# Sheet1.net
KiCad netlist of a schematic drawn in Altium Designer
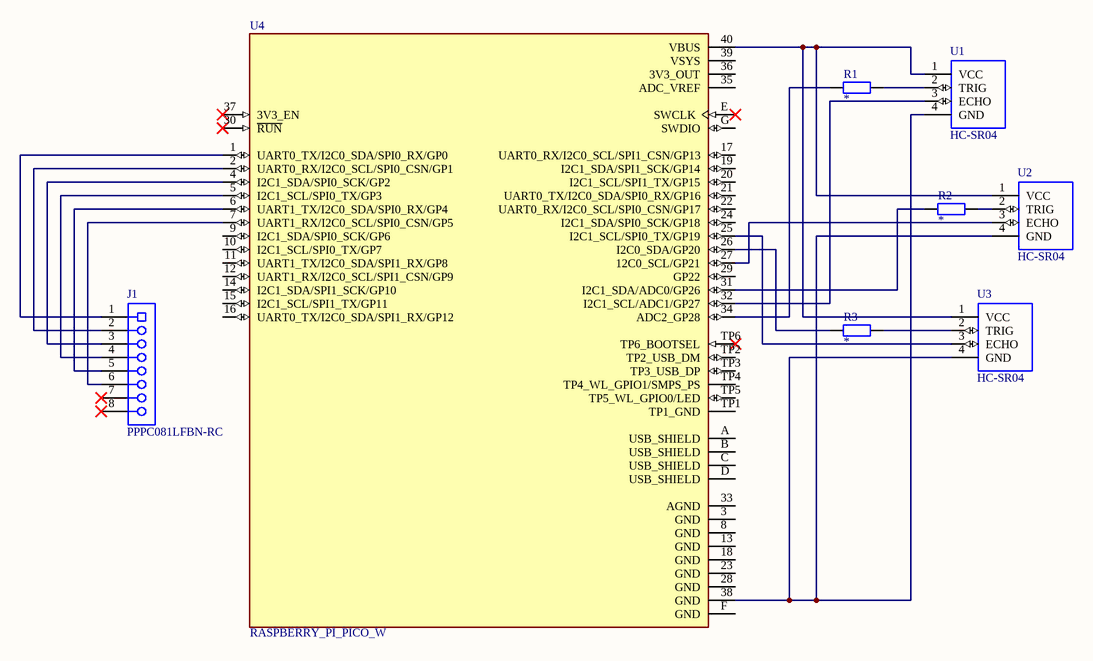
[diagram p0: Sheet1.SchDoc]

(export (version "E")
  (design (tool "Eeschema 10.0.6"))
  (components
    (comp (ref "J1")
      (value "PPPC081LFBN-RC")
      (footprint "SLIN-PPPC081LFBN-RC_V")
      (fields (field (name "MANUFACTURER") "Sullins"))
      (libsource (lib "Akansha Aggarwal") (part "CN-1P-F-R8"))
    )
    (comp (ref "R1")
      (value "*")
      (footprint "AXIAL-0.4")
      (description "Through hole resistor")
      (fields (field (name "PUBLISHER") "Altium Limited"))
      (libsource (lib "EE209_Library") (part "Res_TH_0AX4"))
    )
    (comp (ref "R2")
      (value "*")
      (footprint "AXIAL-0.4")
      (description "Through hole resistor")
      (fields (field (name "PUBLISHER") "Altium Limited"))
      (libsource (lib "EE209_Library") (part "Res_TH_0AX4"))
    )
    (comp (ref "R3")
      (value "*")
      (footprint "AXIAL-0.4")
      (description "Through hole resistor")
      (fields (field (name "PUBLISHER") "Altium Limited"))
      (libsource (lib "EE209_Library") (part "Res_TH_0AX4"))
    )
    (comp (ref "U1")
      (value "HC-SR04")
      (footprint "XCVR_HC-SR04")
      (description "Ultrasonic Sensor Module")
      (libsource (lib "HC-SR04") (part "HC-SR04"))
    )
    (comp (ref "U2")
      (value "HC-SR04")
      (footprint "XCVR_HC-SR04")
      (description "Ultrasonic Sensor Module")
      (libsource (lib "HC-SR04") (part "HC-SR04"))
    )
    (comp (ref "U3")
      (value "HC-SR04")
      (footprint "XCVR_HC-SR04")
      (description "Ultrasonic Sensor Module")
      (libsource (lib "HC-SR04") (part "HC-SR04"))
    )
    (comp (ref "U4")
      (value "RASPBERRY_PI_PICO_W")
      (footprint "MODULE_RASPBERRY_PI_PICO_W")
      (fields (field (name "MF") "Raspberry Pi") (field (name "MP") "RASPBERRY PI PICO W"))
      (libsource (lib "RASPBERRY_PI_PICO_W") (part "RASPBERRY_PI_PICO_W"))
    )
  )
  (nets
    (net (code "1") (name "Net-(U1-ECHO)") (class "Default")
      (node (ref "U1") (pin "3") (pinfunction "ECHO_3") (pintype "bidirectional"))
      (node (ref "U4") (pin "32") (pinfunction "I2C1_SCL/ADC1/GP27_32") (pintype "bidirectional"))
    )
    (net (code "2") (name "Net-(U1-GND)") (class "Default")
      (node (ref "U1") (pin "4") (pinfunction "GND_4") (pintype "power_in"))
      (node (ref "U2") (pin "4") (pinfunction "GND_4") (pintype "power_in"))
      (node (ref "U3") (pin "4") (pinfunction "GND_4") (pintype "power_in"))
      (node (ref "U4") (pin "38") (pinfunction "GND_38") (pintype "power_in"))
    )
    (net (code "3") (name "Net-(U1-TRIG)") (class "Default")
      (node (ref "R1") (pin "2") (pinfunction "2_2") (pintype "passive"))
      (node (ref "U1") (pin "2") (pinfunction "TRIG_2") (pintype "bidirectional"))
    )
    (net (code "4") (name "Net-(U1-VCC)") (class "Default")
      (node (ref "U1") (pin "1") (pinfunction "VCC_1") (pintype "power_in"))
      (node (ref "U2") (pin "1") (pinfunction "VCC_1") (pintype "power_in"))
      (node (ref "U3") (pin "1") (pinfunction "VCC_1") (pintype "power_in"))
      (node (ref "U4") (pin "40") (pinfunction "VBUS_40") (pintype "power_in"))
    )
    (net (code "5") (name "Net-(U2-ECHO)") (class "Default")
      (node (ref "U2") (pin "3") (pinfunction "ECHO_3") (pintype "bidirectional"))
      (node (ref "U4") (pin "27") (pinfunction "12C0_SCL/GP21_27") (pintype "bidirectional"))
    )
    (net (code "6") (name "Net-(U2-TRIG)") (class "Default")
      (node (ref "R2") (pin "2") (pinfunction "2_2") (pintype "passive"))
      (node (ref "U2") (pin "2") (pinfunction "TRIG_2") (pintype "bidirectional"))
    )
    (net (code "7") (name "Net-(U3-ECHO)") (class "Default")
      (node (ref "U3") (pin "3") (pinfunction "ECHO_3") (pintype "bidirectional"))
      (node (ref "U4") (pin "25") (pinfunction "I2C1_SCL/SPI0_TX/GP19_25") (pintype "bidirectional"))
    )
    (net (code "8") (name "Net-(U3-TRIG)") (class "Default")
      (node (ref "R3") (pin "2") (pinfunction "2_2") (pintype "passive"))
      (node (ref "U3") (pin "2") (pinfunction "TRIG_2") (pintype "bidirectional"))
    )
    (net (code "9") (name "Net-(U4-ADC2_GP28)") (class "Default")
      (node (ref "R1") (pin "1") (pinfunction "1_1") (pintype "passive"))
      (node (ref "U4") (pin "34") (pinfunction "ADC2_GP28_34") (pintype "bidirectional"))
    )
    (net (code "10") (name "Net-(U4-I2C0_SDA{slash}GP20)") (class "Default")
      (node (ref "R3") (pin "1") (pinfunction "1_1") (pintype "passive"))
      (node (ref "U4") (pin "26") (pinfunction "I2C0_SDA/GP20_26") (pintype "bidirectional"))
    )
    (net (code "11") (name "Net-(U4-I2C1_SCL{slash}SPI0_TX{slash}GP3)") (class "Default")
      (node (ref "J1") (pin "4") (pinfunction "4_4") (pintype "passive"))
      (node (ref "U4") (pin "5") (pinfunction "I2C1_SCL/SPI0_TX/GP3_5") (pintype "bidirectional"))
    )
    (net (code "12") (name "Net-(U4-I2C1_SDA{slash}ADC0{slash}GP26)") (class "Default")
      (node (ref "R2") (pin "1") (pinfunction "1_1") (pintype "passive"))
      (node (ref "U4") (pin "31") (pinfunction "I2C1_SDA/ADC0/GP26_31") (pintype "bidirectional"))
    )
    (net (code "13") (name "Net-(U4-I2C1_SDA{slash}SPI0_SCK{slash}GP2)") (class "Default")
      (node (ref "J1") (pin "3") (pinfunction "3_3") (pintype "passive"))
      (node (ref "U4") (pin "4") (pinfunction "I2C1_SDA/SPI0_SCK/GP2_4") (pintype "bidirectional"))
    )
    (net (code "14") (name "Net-(U4-UART0_RX{slash}I2C0_SCL{slash}SPI0_CSN{slash}GP1)") (class "Default")
      (node (ref "J1") (pin "2") (pinfunction "2_2") (pintype "passive"))
      (node (ref "U4") (pin "2") (pinfunction "UART0_RX/I2C0_SCL/SPI0_CSN/GP1_2") (pintype "bidirectional"))
    )
    (net (code "15") (name "Net-(U4-UART0_TX{slash}I2C0_SDA{slash}SPI0_RX{slash}GP0)") (class "Default")
      (node (ref "J1") (pin "1") (pinfunction "1_1") (pintype "passive"))
      (node (ref "U4") (pin "1") (pinfunction "UART0_TX/I2C0_SDA/SPI0_RX/GP0_1") (pintype "bidirectional"))
    )
    (net (code "16") (name "Net-(U4-UART1_RX{slash}I2C0_SCL{slash}SPI0_CSN{slash}GP5)") (class "Default")
      (node (ref "J1") (pin "6") (pinfunction "6_6") (pintype "passive"))
      (node (ref "U4") (pin "7") (pinfunction "UART1_RX/I2C0_SCL/SPI0_CSN/GP5_7") (pintype "bidirectional"))
    )
    (net (code "17") (name "Net-(U4-UART1_TX{slash}I2C0_SDA{slash}SPI0_RX{slash}GP4)") (class "Default")
      (node (ref "J1") (pin "5") (pinfunction "5_5") (pintype "passive"))
      (node (ref "U4") (pin "6") (pinfunction "UART1_TX/I2C0_SDA/SPI0_RX/GP4_6") (pintype "bidirectional"))
    )
    (net (code "18") (name "unconnected-(J1-Pad7)") (class "Default")
      (node (ref "J1") (pin "7") (pinfunction "7_7") (pintype "passive+no_connect"))
    )
    (net (code "19") (name "unconnected-(J1-Pad8)") (class "Default")
      (node (ref "J1") (pin "8") (pinfunction "8_8") (pintype "passive+no_connect"))
    )
    (net (code "20") (name "unconnected-(U4-3V3_EN-Pad37)") (class "Default")
      (node (ref "U4") (pin "37") (pinfunction "3V3_EN_37") (pintype "input+no_connect"))
    )
    (net (code "21") (name "unconnected-(U4-3V3_OUT-Pad36)") (class "Default")
      (node (ref "U4") (pin "36") (pinfunction "3V3_OUT_36") (pintype "power_in"))
    )
    (net (code "22") (name "unconnected-(U4-ADC_VREF-Pad35)") (class "Default")
      (node (ref "U4") (pin "35") (pinfunction "ADC_VREF_35") (pintype "power_in"))
    )
    (net (code "23") (name "unconnected-(U4-AGND-Pad33)") (class "Default")
      (node (ref "U4") (pin "33") (pinfunction "AGND_33") (pintype "power_in"))
    )
    (net (code "24") (name "unconnected-(U4-GND-Pad3)") (class "Default")
      (node (ref "U4") (pin "3") (pinfunction "GND_3") (pintype "power_in"))
    )
    (net (code "25") (name "unconnected-(U4-GND-Pad8)") (class "Default")
      (node (ref "U4") (pin "8") (pinfunction "GND_8") (pintype "power_in"))
    )
    (net (code "26") (name "unconnected-(U4-GND-Pad13)") (class "Default")
      (node (ref "U4") (pin "13") (pinfunction "GND_13") (pintype "power_in"))
    )
    (net (code "27") (name "unconnected-(U4-GND-Pad18)") (class "Default")
      (node (ref "U4") (pin "18") (pinfunction "GND_18") (pintype "power_in"))
    )
    (net (code "28") (name "unconnected-(U4-GND-Pad23)") (class "Default")
      (node (ref "U4") (pin "23") (pinfunction "GND_23") (pintype "power_in"))
    )
    (net (code "29") (name "unconnected-(U4-GND-Pad28)") (class "Default")
      (node (ref "U4") (pin "28") (pinfunction "GND_28") (pintype "power_in"))
    )
    (net (code "30") (name "unconnected-(U4-GND-PadF)") (class "Default")
      (node (ref "U4") (pin "F") (pinfunction "GND_F") (pintype "power_in"))
    )
    (net (code "31") (name "unconnected-(U4-GP22-Pad29)") (class "Default")
      (node (ref "U4") (pin "29") (pinfunction "GP22_29") (pintype "bidirectional"))
    )
    (net (code "32") (name "unconnected-(U4-I2C1_SCL{slash}SPI0_TX{slash}GP7-Pad10)") (class "Default")
      (node (ref "U4") (pin "10") (pinfunction "I2C1_SCL/SPI0_TX/GP7_10") (pintype "bidirectional"))
    )
    (net (code "33") (name "unconnected-(U4-I2C1_SCL{slash}SPI1_TX{slash}GP11-Pad15)") (class "Default")
      (node (ref "U4") (pin "15") (pinfunction "I2C1_SCL/SPI1_TX/GP11_15") (pintype "bidirectional"))
    )
    (net (code "34") (name "unconnected-(U4-I2C1_SCL{slash}SPI1_TX{slash}GP15-Pad20)") (class "Default")
      (node (ref "U4") (pin "20") (pinfunction "I2C1_SCL/SPI1_TX/GP15_20") (pintype "bidirectional"))
    )
    (net (code "35") (name "unconnected-(U4-I2C1_SDA{slash}SPI0_SCK{slash}GP6-Pad9)") (class "Default")
      (node (ref "U4") (pin "9") (pinfunction "I2C1_SDA/SPI0_SCK/GP6_9") (pintype "bidirectional"))
    )
    (net (code "36") (name "unconnected-(U4-I2C1_SDA{slash}SPI0_SCK{slash}GP18-Pad24)") (class "Default")
      (node (ref "U4") (pin "24") (pinfunction "I2C1_SDA/SPI0_SCK/GP18_24") (pintype "bidirectional"))
    )
    (net (code "37") (name "unconnected-(U4-I2C1_SDA{slash}SPI1_SCK{slash}GP10-Pad14)") (class "Default")
      (node (ref "U4") (pin "14") (pinfunction "I2C1_SDA/SPI1_SCK/GP10_14") (pintype "bidirectional"))
    )
    (net (code "38") (name "unconnected-(U4-I2C1_SDA{slash}SPI1_SCK{slash}GP14-Pad19)") (class "Default")
      (node (ref "U4") (pin "19") (pinfunction "I2C1_SDA/SPI1_SCK/GP14_19") (pintype "bidirectional"))
    )
    (net (code "39") (name "unconnected-(U4-SWCLK-PadE)") (class "Default")
      (node (ref "U4") (pin "E") (pinfunction "SWCLK_E") (pintype "input+no_connect"))
    )
    (net (code "40") (name "unconnected-(U4-SWDIO-PadG)") (class "Default")
      (node (ref "U4") (pin "G") (pinfunction "SWDIO_G") (pintype "bidirectional"))
    )
    (net (code "41") (name "unconnected-(U4-TP1_GND-PadTP1)") (class "Default")
      (node (ref "U4") (pin "TP1") (pinfunction "TP1_GND_TP1") (pintype "power_in"))
    )
    (net (code "42") (name "unconnected-(U4-TP2_USB_DM-PadTP2)") (class "Default")
      (node (ref "U4") (pin "TP2") (pinfunction "TP2_USB_DM_TP2") (pintype "bidirectional"))
    )
    (net (code "43") (name "unconnected-(U4-TP3_USB_DP-PadTP3)") (class "Default")
      (node (ref "U4") (pin "TP3") (pinfunction "TP3_USB_DP_TP3") (pintype "bidirectional"))
    )
    (net (code "44") (name "unconnected-(U4-TP4_WL_GPIO1{slash}SMPS_PS-PadTP4)") (class "Default")
      (node (ref "U4") (pin "TP4") (pinfunction "TP4_WL_GPIO1/SMPS_PS_TP4") (pintype "passive"))
    )
    (net (code "45") (name "unconnected-(U4-TP5_WL_GPIO0{slash}LED-PadTP5)") (class "Default")
      (node (ref "U4") (pin "TP5") (pinfunction "TP5_WL_GPIO0/LED_TP5") (pintype "bidirectional"))
    )
    (net (code "46") (name "unconnected-(U4-TP6_BOOTSEL-PadTP6)") (class "Default")
      (node (ref "U4") (pin "TP6") (pinfunction "TP6_BOOTSEL_TP6") (pintype "input+no_connect"))
    )
    (net (code "47") (name "unconnected-(U4-UART0_RX{slash}I2C0_SCL{slash}SPI0_CSN{slash}GP17-Pad22)") (class "Default")
      (node (ref "U4") (pin "22") (pinfunction "UART0_RX/I2C0_SCL/SPI0_CSN/GP17_22") (pintype "bidirectional"))
    )
    (net (code "48") (name "unconnected-(U4-UART0_RX{slash}I2C0_SCL{slash}SPI1_CSN{slash}GP13-Pad17)") (class "Default")
      (node (ref "U4") (pin "17") (pinfunction "UART0_RX/I2C0_SCL/SPI1_CSN/GP13_17") (pintype "bidirectional"))
    )
    (net (code "49") (name "unconnected-(U4-UART0_TX{slash}I2C0_SDA{slash}SPI0_RX{slash}GP16-Pad21)") (class "Default")
      (node (ref "U4") (pin "21") (pinfunction "UART0_TX/I2C0_SDA/SPI0_RX/GP16_21") (pintype "bidirectional"))
    )
    (net (code "50") (name "unconnected-(U4-UART0_TX{slash}I2C0_SDA{slash}SPI1_RX{slash}GP12-Pad16)") (class "Default")
      (node (ref "U4") (pin "16") (pinfunction "UART0_TX/I2C0_SDA/SPI1_RX/GP12_16") (pintype "bidirectional"))
    )
    (net (code "51") (name "unconnected-(U4-UART1_RX{slash}I2C0_SCL{slash}SPI1_CSN{slash}GP9-Pad12)") (class "Default")
      (node (ref "U4") (pin "12") (pinfunction "UART1_RX/I2C0_SCL/SPI1_CSN/GP9_12") (pintype "bidirectional"))
    )
    (net (code "52") (name "unconnected-(U4-UART1_TX{slash}I2C0_SDA{slash}SPI1_RX{slash}GP8-Pad11)") (class "Default")
      (node (ref "U4") (pin "11") (pinfunction "UART1_TX/I2C0_SDA/SPI1_RX/GP8_11") (pintype "bidirectional"))
    )
    (net (code "53") (name "unconnected-(U4-USB_SHIELD-PadA)") (class "Default")
      (node (ref "U4") (pin "A") (pinfunction "USB_SHIELD_A") (pintype "power_in"))
    )
    (net (code "54") (name "unconnected-(U4-USB_SHIELD-PadB)") (class "Default")
      (node (ref "U4") (pin "B") (pinfunction "USB_SHIELD_B") (pintype "power_in"))
    )
    (net (code "55") (name "unconnected-(U4-USB_SHIELD-PadC)") (class "Default")
      (node (ref "U4") (pin "C") (pinfunction "USB_SHIELD_C") (pintype "power_in"))
    )
    (net (code "56") (name "unconnected-(U4-USB_SHIELD-PadD)") (class "Default")
      (node (ref "U4") (pin "D") (pinfunction "USB_SHIELD_D") (pintype "power_in"))
    )
    (net (code "57") (name "unconnected-(U4-VSYS-Pad39)") (class "Default")
      (node (ref "U4") (pin "39") (pinfunction "VSYS_39") (pintype "power_in"))
    )
    (net (code "58") (name "unconnected-(U4-~{RUN}-Pad30)") (class "Default")
      (node (ref "U4") (pin "30") (pinfunction "~{RUN}_30") (pintype "input+no_connect"))
    )
  )
)
